# Music_IN_Balance_NEXT_GEN_2026-02-06.net
KiCad netlist of a schematic drawn in EasyEDA Pro
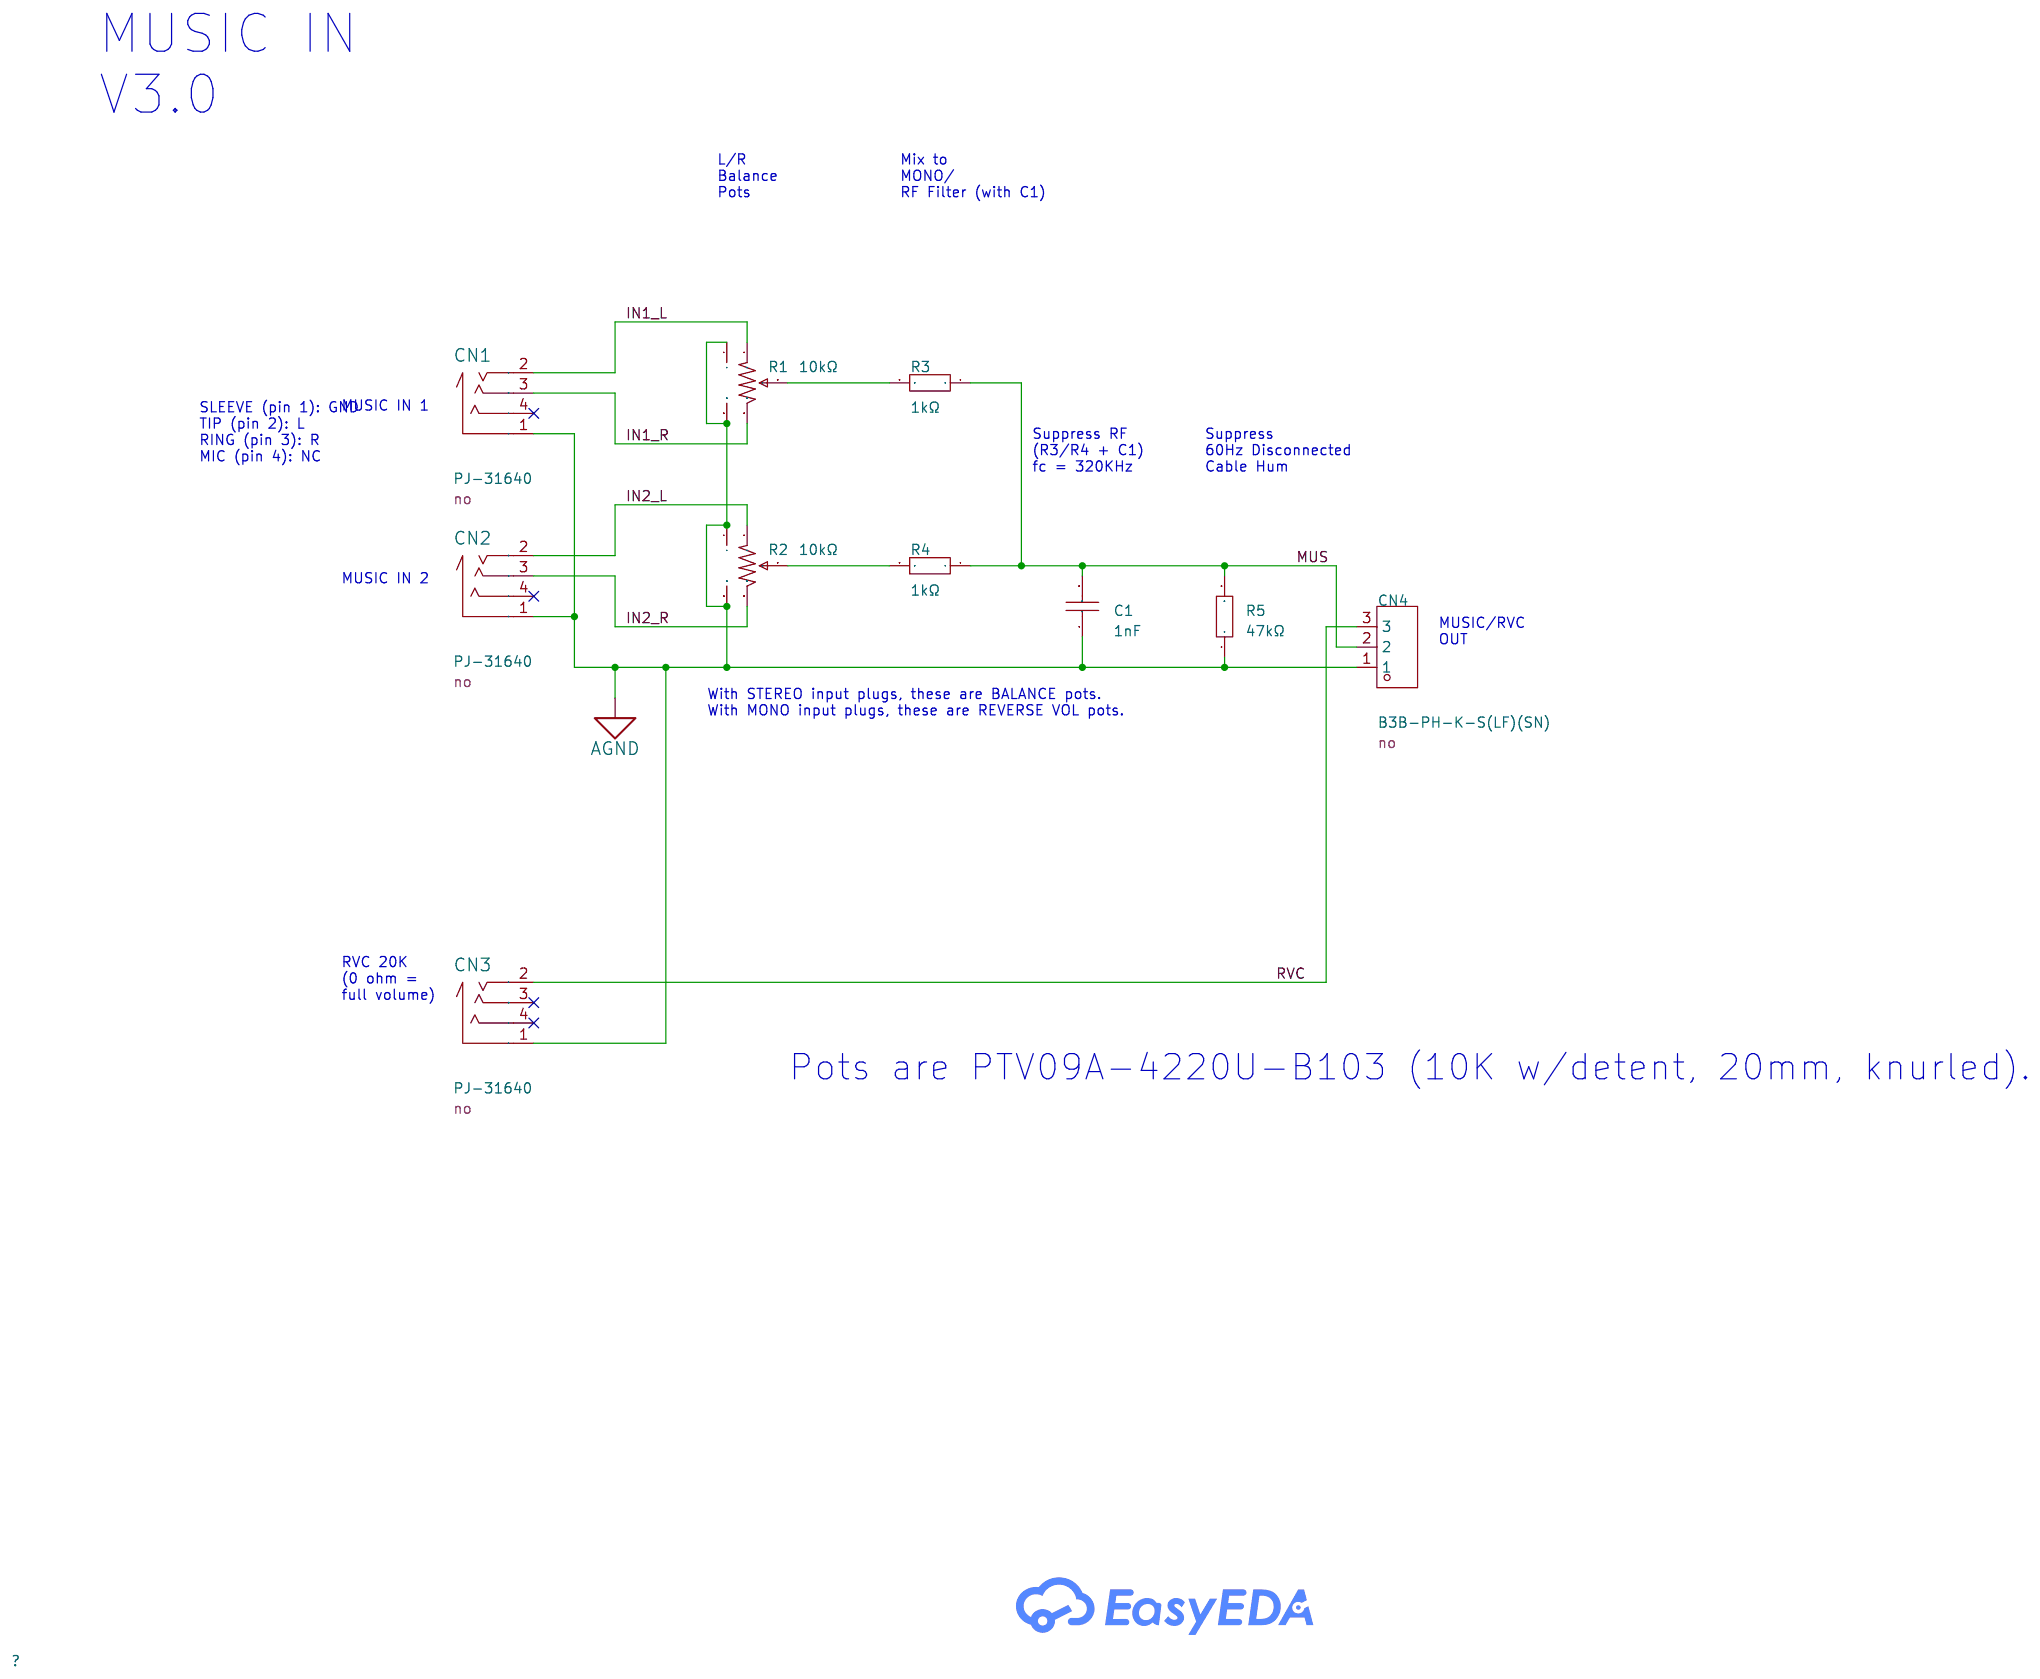
[diagram p0: schematic sheet]

(export (version "E")
  (design (tool "Eeschema 10.0.6"))
  (components
    (comp (ref "C1")
      (value "1nF")
      (footprint "easyedapro:C0402")
      (description "Capacitance:1nF Tolerance:±10% Tolerance:±10% Voltage Rating:50V Temperature Coefficient:X7R")
      (fields (field (name "Manufacturer Part") "0402B102K500NT") (field (name "Manufacturer") "FH(风华)"))
      (libsource (lib "easyedapro") (part "0402B102K500NT"))
    )
    (comp (ref "CN1")
      (value "PJ-31640")
      (footprint "easyedapro:AUDIO-TH_XKB_PJ-31640")
      (fields (field (name "Manufacturer") "XKB Connectivity(中国星坤)") (field (name "Add into BOM") "no"))
      (libsource (lib "easyedapro") (part "PJ-31640"))
    )
    (comp (ref "CN2")
      (value "PJ-31640")
      (footprint "easyedapro:AUDIO-TH_XKB_PJ-31640")
      (fields (field (name "Manufacturer") "XKB Connectivity(中国星坤)") (field (name "Add into BOM") "no"))
      (libsource (lib "easyedapro") (part "PJ-31640"))
    )
    (comp (ref "CN3")
      (value "PJ-31640")
      (footprint "easyedapro:AUDIO-TH_XKB_PJ-31640")
      (fields (field (name "Manufacturer") "XKB Connectivity(中国星坤)") (field (name "Add into BOM") "no"))
      (libsource (lib "easyedapro") (part "PJ-31640"))
    )
    (comp (ref "CN4")
      (value "B3B-PH-K-S(LF)(SN)")
      (footprint "easyedapro:CONN-TH_B3B-PH-K-S")
      (fields (field (name "Manufacturer") "JST") (field (name "Add into BOM") "no"))
      (libsource (lib "easyedapro") (part "B3B-PH-K-S(LF)(SN)"))
    )
    (comp (ref "R1")
      (value "10kΩ")
      (footprint "easyedapro:SW-TH_PTV09A-4015F-B502")
      (fields (field (name "Manufacturer Part") "PTV09A-4220U-B103") (field (name "Manufacturer") "BOURNS"))
      (libsource (lib "easyedapro") (part "PTV09A-4220U-B103"))
    )
    (comp (ref "R2")
      (value "10kΩ")
      (footprint "easyedapro:SW-TH_PTV09A-4015F-B502")
      (fields (field (name "Manufacturer Part") "PTV09A-4220U-B103") (field (name "Manufacturer") "BOURNS"))
      (libsource (lib "easyedapro") (part "PTV09A-4220U-B103"))
    )
    (comp (ref "R3")
      (value "1kΩ")
      (fields
        (field (name "Manufacturer Part") "0402WGF1001TCE")
        (field (name "Manufacturer") "UNI-ROYAL(厚声)")
      )
      (libsource (lib "easyedapro") (part "Res"))
    )
    (comp (ref "R4")
      (value "1kΩ")
      (fields
        (field (name "Manufacturer Part") "0402WGF1001TCE")
        (field (name "Manufacturer") "UNI-ROYAL(厚声)")
      )
      (libsource (lib "easyedapro") (part "Res"))
    )
    (comp (ref "R5")
      (value "47kΩ")
      (footprint "easyedapro:R0402")
      (fields
        (field (name "Manufacturer Part") "0402WGF4702TCE")
        (field (name "Manufacturer") "UNI-ROYAL(厚声)")
      )
      (libsource (lib "easyedapro") (part "0402WGF4702TCE"))
    )
  )
  (nets
    (net (code "1") (name "/IN1_L") (class "Default")
      (node (ref "CN1") (pin "2") (pinfunction "2_2") (pintype "input"))
      (node (ref "R1") (pin "1") (pinfunction "1_1") (pintype "unspecified"))
    )
    (net (code "2") (name "/IN1_R") (class "Default")
      (node (ref "CN1") (pin "3") (pinfunction "3_3") (pintype "input"))
      (node (ref "R1") (pin "3") (pinfunction "3_3") (pintype "unspecified"))
    )
    (net (code "3") (name "/IN2_L") (class "Default")
      (node (ref "CN2") (pin "2") (pinfunction "2_2") (pintype "input"))
      (node (ref "R2") (pin "1") (pinfunction "1_1") (pintype "unspecified"))
    )
    (net (code "4") (name "/IN2_R") (class "Default")
      (node (ref "CN2") (pin "3") (pinfunction "3_3") (pintype "input"))
      (node (ref "R2") (pin "3") (pinfunction "3_3") (pintype "unspecified"))
    )
    (net (code "5") (name "/MUS") (class "Default")
      (node (ref "C1") (pin "2") (pinfunction "2_2") (pintype "input"))
      (node (ref "CN4") (pin "2") (pinfunction "2_2") (pintype "unspecified"))
      (node (ref "R3") (pin "1") (pinfunction "1_1") (pintype "input"))
      (node (ref "R4") (pin "1") (pinfunction "1_1") (pintype "input"))
      (node (ref "R5") (pin "2") (pinfunction "2_2") (pintype "input"))
    )
    (net (code "6") (name "/RVC") (class "Default")
      (node (ref "CN3") (pin "2") (pinfunction "2_2") (pintype "input"))
      (node (ref "CN4") (pin "3") (pinfunction "3_3") (pintype "unspecified"))
    )
    (net (code "7") (name "AGND") (class "Default")
      (node (ref "C1") (pin "1") (pinfunction "1_1") (pintype "input"))
      (node (ref "CN1") (pin "1") (pinfunction "1_1") (pintype "input"))
      (node (ref "CN2") (pin "1") (pinfunction "1_1") (pintype "input"))
      (node (ref "CN3") (pin "1") (pinfunction "1_1") (pintype "input"))
      (node (ref "CN4") (pin "1") (pinfunction "1_1") (pintype "unspecified"))
      (node (ref "R1") (pin "4") (pinfunction "4_4") (pintype "unspecified"))
      (node (ref "R1") (pin "5") (pinfunction "5_5") (pintype "unspecified"))
      (node (ref "R2") (pin "4") (pinfunction "4_4") (pintype "unspecified"))
      (node (ref "R2") (pin "5") (pinfunction "5_5") (pintype "unspecified"))
      (node (ref "R5") (pin "1") (pinfunction "1_1") (pintype "input"))
    )
    (net (code "8") (name "Net-(R1-Pad2)") (class "Default")
      (node (ref "R1") (pin "2") (pinfunction "2_2") (pintype "unspecified"))
      (node (ref "R3") (pin "2") (pinfunction "2_2") (pintype "input"))
    )
    (net (code "9") (name "Net-(R2-Pad2)") (class "Default")
      (node (ref "R2") (pin "2") (pinfunction "2_2") (pintype "unspecified"))
      (node (ref "R4") (pin "2") (pinfunction "2_2") (pintype "input"))
    )
    (net (code "10") (name "unconnected-(CN1-Pad4)") (class "Default")
      (node (ref "CN1") (pin "4") (pinfunction "4_4") (pintype "input+no_connect"))
    )
    (net (code "11") (name "unconnected-(CN2-Pad4)") (class "Default")
      (node (ref "CN2") (pin "4") (pinfunction "4_4") (pintype "input+no_connect"))
    )
    (net (code "12") (name "unconnected-(CN3-Pad3)") (class "Default")
      (node (ref "CN3") (pin "3") (pinfunction "3_3") (pintype "input+no_connect"))
    )
    (net (code "13") (name "unconnected-(CN3-Pad4)") (class "Default")
      (node (ref "CN3") (pin "4") (pinfunction "4_4") (pintype "input+no_connect"))
    )
  )
)
